# Board_4x8-Prototype_v20160405.net
KiCad netlist of a schematic drawn in EAGLE
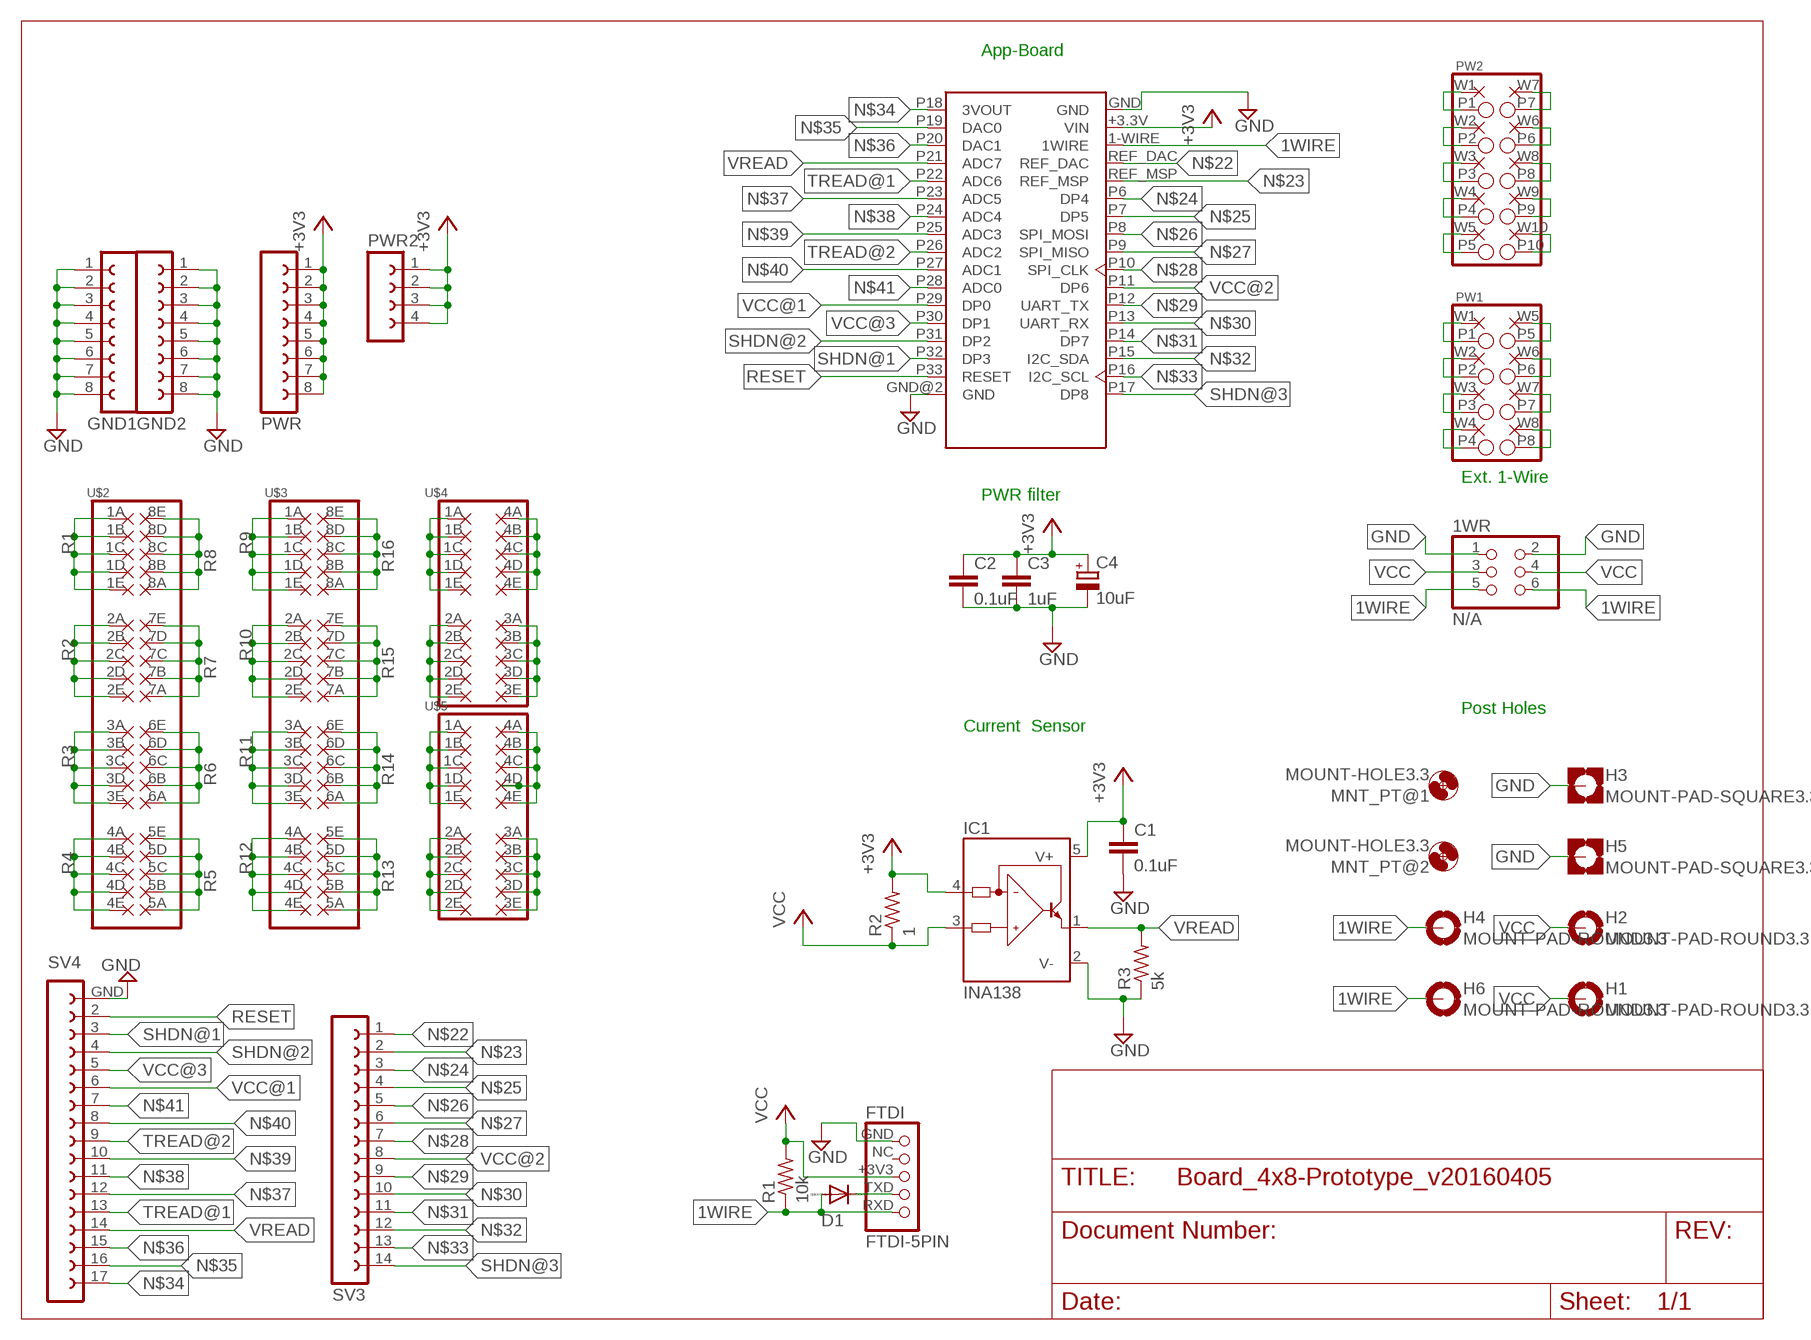
[diagram p0: schematic, sheet 1]

(export (version "E")
  (design (tool "Eeschema 10.0.6"))
  (components
    (comp (ref "1WR")
      (value "N/A")
      (footprint "eagle-import:2X03")
      (libsource (lib "eagle-import") (part "PINHD-2X3"))
    )
    (comp (ref "C1")
      (value "0.1uF")
      (footprint "eagle-import:C0805")
      (libsource (lib "eagle-import") (part "C-EUC0805"))
    )
    (comp (ref "C2")
      (value "0.1uF")
      (footprint "eagle-import:C0603")
      (libsource (lib "eagle-import") (part "C-EUC0603"))
    )
    (comp (ref "C3")
      (value "1uF")
      (footprint "eagle-import:C0603")
      (libsource (lib "eagle-import") (part "C-EUC0603"))
    )
    (comp (ref "C4")
      (value "10uF")
      (footprint "eagle-import:SMC_B")
      (libsource (lib "eagle-import") (part "CPOL-EUSMCB"))
    )
    (comp (ref "D1")
      (value "1N4148DO35-7")
      (footprint "eagle-import:DO35-7")
      (libsource (lib "eagle-import") (part "1N4148DO35-7"))
    )
    (comp (ref "FTDI")
      (value "FTDI-5PIN")
      (footprint "eagle-import:1_05X2MM")
      (libsource (lib "eagle-import") (part "FTDI-5PIN"))
    )
    (comp (ref "GND1")
      (value "FE08-1-GND")
      (footprint "eagle-import:FE08-GND")
      (libsource (lib "eagle-import") (part "FE08-1-GND"))
    )
    (comp (ref "GND2")
      (value "FE08-1-GND")
      (footprint "eagle-import:FE08-GND")
      (libsource (lib "eagle-import") (part "FE08-1-GND"))
    )
    (comp (ref "H1")
      (value "MOUNT-PAD-ROUND3.3")
      (footprint "eagle-import:3,3-PAD")
      (libsource (lib "eagle-import") (part "MOUNT-PAD-ROUND3.3"))
    )
    (comp (ref "H2")
      (value "MOUNT-PAD-ROUND3.3")
      (footprint "eagle-import:3,3-PAD")
      (libsource (lib "eagle-import") (part "MOUNT-PAD-ROUND3.3"))
    )
    (comp (ref "H3")
      (value "MOUNT-PAD-SQUARE3.3")
      (footprint "eagle-import:3,3-PAD-SQUARE")
      (libsource (lib "eagle-import") (part "MOUNT-PAD-SQUARE3.3"))
    )
    (comp (ref "H4")
      (value "MOUNT-PAD-ROUND3.3")
      (footprint "eagle-import:3,3-PAD")
      (libsource (lib "eagle-import") (part "MOUNT-PAD-ROUND3.3"))
    )
    (comp (ref "H5")
      (value "MOUNT-PAD-SQUARE3.3")
      (footprint "eagle-import:3,3-PAD-SQUARE")
      (libsource (lib "eagle-import") (part "MOUNT-PAD-SQUARE3.3"))
    )
    (comp (ref "H6")
      (value "MOUNT-PAD-ROUND3.3")
      (footprint "eagle-import:3,3-PAD")
      (libsource (lib "eagle-import") (part "MOUNT-PAD-ROUND3.3"))
    )
    (comp (ref "IC1")
      (value "INA138")
      (footprint "eagle-import:SOT23-5")
      (fields (field (name "MF") "TEXAS INSTRUMENTS") (field (name "MPN") "INA138NA/250"))
      (libsource (lib "eagle-import") (part "INA138"))
    )
    (comp (ref "MNT_PT@1")
      (value "MOUNT-HOLE3.3")
      (footprint "eagle-import:3,3")
      (libsource (lib "eagle-import") (part "MOUNT-HOLE3.3"))
    )
    (comp (ref "MNT_PT@2")
      (value "MOUNT-HOLE3.3")
      (footprint "eagle-import:3,3")
      (libsource (lib "eagle-import") (part "MOUNT-HOLE3.3"))
    )
    (comp (ref "PW1")
      (value "PIN-WIRE-2X8")
      (footprint "eagle-import:2X8")
      (libsource (lib "eagle-import") (part "PIN-WIRE-2X8"))
    )
    (comp (ref "PW2")
      (value "PIN-WIRE-2X10")
      (footprint "eagle-import:2X10")
      (libsource (lib "eagle-import") (part "PIN-WIRE-2X10"))
    )
    (comp (ref "PWR")
      (value "FE08-1")
      (footprint "eagle-import:FE08")
      (libsource (lib "eagle-import") (part "FE08-1"))
    )
    (comp (ref "PWR2")
      (value "FE04-1")
      (footprint "eagle-import:FE04-1")
      (libsource (lib "eagle-import") (part "FE04-1"))
    )
    (comp (ref "R1")
      (value "10k")
      (footprint "eagle-import:0207_7")
      (libsource (lib "eagle-import") (part "R-US_0207/7"))
    )
    (comp (ref "R2")
      (value "1")
      (footprint "eagle-import:R0603")
      (libsource (lib "eagle-import") (part "R-US_R0603"))
    )
    (comp (ref "R3")
      (value "5k")
      (footprint "eagle-import:R0603")
      (libsource (lib "eagle-import") (part "R-US_R0603"))
    )
    (comp (ref "SV3")
      (value "FE14-1_ABBO")
      (footprint "eagle-import:FE14-1_ABBO")
      (libsource (lib "eagle-import") (part "FE14-1_ABBO"))
    )
    (comp (ref "SV4")
      (value "FE17-1_ABBO")
      (footprint "eagle-import:FE17-1_ABBO")
      (libsource (lib "eagle-import") (part "FE17-1_ABBO"))
    )
    (comp (ref "U$1")
      (value "App-Board 1.2/1.3")
      (footprint "eagle-import:APPCORE_RECEIVER")
      (libsource (lib "eagle-import") (part "APP_CORE"))
    )
    (comp (ref "U$2")
      (value "PROTO-5X8")
      (footprint "eagle-import:PROTO-2X05")
      (libsource (lib "eagle-import") (part "PROTO-5X8"))
    )
    (comp (ref "U$3")
      (value "PROTO-5X8")
      (footprint "eagle-import:PROTO-2X05")
      (libsource (lib "eagle-import") (part "PROTO-5X8"))
    )
    (comp (ref "U$4")
      (value "PROTO-4X5")
      (footprint "eagle-import:PROTO-4X05")
      (libsource (lib "eagle-import") (part "PROTO-4X5"))
    )
    (comp (ref "U$5")
      (value "PROTO-4X5")
      (footprint "eagle-import:PROTO-4X05")
      (libsource (lib "eagle-import") (part "PROTO-4X5"))
    )
  )
  (nets
    (net (code "1") (name "+3V3") (class "Default")
      (node (ref "C1") (pin "1") (pinfunction "1_1") (pintype "passive"))
      (node (ref "C2") (pin "1") (pinfunction "1_1") (pintype "passive"))
      (node (ref "C3") (pin "1") (pinfunction "1_1") (pintype "passive"))
      (node (ref "C4") (pin "+") (pinfunction "+_+") (pintype "passive"))
      (node (ref "IC1") (pin "4") (pinfunction "IN-_4") (pintype "input"))
      (node (ref "IC1") (pin "5") (pinfunction "V+_5") (pintype "power_in"))
      (node (ref "PWR") (pin "1") (pinfunction "1_1") (pintype "passive"))
      (node (ref "PWR") (pin "2") (pinfunction "2_2") (pintype "passive"))
      (node (ref "PWR") (pin "3") (pinfunction "3_3") (pintype "passive"))
      (node (ref "PWR") (pin "4") (pinfunction "4_4") (pintype "passive"))
      (node (ref "PWR") (pin "5") (pinfunction "5_5") (pintype "passive"))
      (node (ref "PWR") (pin "6") (pinfunction "6_6") (pintype "passive"))
      (node (ref "PWR") (pin "7") (pinfunction "7_7") (pintype "passive"))
      (node (ref "PWR") (pin "8") (pinfunction "8_8") (pintype "passive"))
      (node (ref "PWR2") (pin "1") (pinfunction "1_1") (pintype "passive"))
      (node (ref "PWR2") (pin "2") (pinfunction "2_2") (pintype "passive"))
      (node (ref "PWR2") (pin "3") (pinfunction "3_3") (pintype "passive"))
      (node (ref "PWR2") (pin "4") (pinfunction "4_4") (pintype "passive"))
      (node (ref "R2") (pin "2") (pinfunction "2_2") (pintype "passive"))
      (node (ref "U$1") (pin "+3.3V") (pinfunction "VIN_+3.3V") (pintype "power_in"))
    )
    (net (code "2") (name "/R1") (class "Default")
      (node (ref "U$2") (pin "1A") (pinfunction "1A_1A") (pintype "passive"))
      (node (ref "U$2") (pin "1B") (pinfunction "1B_1B") (pintype "passive"))
      (node (ref "U$2") (pin "1C") (pinfunction "1C_1C") (pintype "passive"))
      (node (ref "U$2") (pin "1D") (pinfunction "1D_1D") (pintype "passive"))
      (node (ref "U$2") (pin "1E") (pinfunction "1E_1E") (pintype "passive"))
    )
    (net (code "3") (name "/R2") (class "Default")
      (node (ref "U$2") (pin "2A") (pinfunction "2A_2A") (pintype "passive"))
      (node (ref "U$2") (pin "2B") (pinfunction "2B_2B") (pintype "passive"))
      (node (ref "U$2") (pin "2C") (pinfunction "2C_2C") (pintype "passive"))
      (node (ref "U$2") (pin "2D") (pinfunction "2D_2D") (pintype "passive"))
      (node (ref "U$2") (pin "2E") (pinfunction "2E_2E") (pintype "passive"))
    )
    (net (code "4") (name "/R3") (class "Default")
      (node (ref "U$2") (pin "3A") (pinfunction "3A_3A") (pintype "passive"))
      (node (ref "U$2") (pin "3B") (pinfunction "3B_3B") (pintype "passive"))
      (node (ref "U$2") (pin "3C") (pinfunction "3C_3C") (pintype "passive"))
      (node (ref "U$2") (pin "3D") (pinfunction "3D_3D") (pintype "passive"))
      (node (ref "U$2") (pin "3E") (pinfunction "3E_3E") (pintype "passive"))
    )
    (net (code "5") (name "/R4") (class "Default")
      (node (ref "U$2") (pin "4A") (pinfunction "4A_4A") (pintype "passive"))
      (node (ref "U$2") (pin "4B") (pinfunction "4B_4B") (pintype "passive"))
      (node (ref "U$2") (pin "4C") (pinfunction "4C_4C") (pintype "passive"))
      (node (ref "U$2") (pin "4D") (pinfunction "4D_4D") (pintype "passive"))
      (node (ref "U$2") (pin "4E") (pinfunction "4E_4E") (pintype "passive"))
    )
    (net (code "6") (name "/R5") (class "Default")
      (node (ref "U$2") (pin "5A") (pinfunction "5A_5A") (pintype "passive"))
      (node (ref "U$2") (pin "5B") (pinfunction "5B_5B") (pintype "passive"))
      (node (ref "U$2") (pin "5C") (pinfunction "5C_5C") (pintype "passive"))
      (node (ref "U$2") (pin "5D") (pinfunction "5D_5D") (pintype "passive"))
      (node (ref "U$2") (pin "5E") (pinfunction "5E_5E") (pintype "passive"))
    )
    (net (code "7") (name "/R6") (class "Default")
      (node (ref "U$2") (pin "6A") (pinfunction "6A_6A") (pintype "passive"))
      (node (ref "U$2") (pin "6B") (pinfunction "6B_6B") (pintype "passive"))
      (node (ref "U$2") (pin "6C") (pinfunction "6C_6C") (pintype "passive"))
      (node (ref "U$2") (pin "6D") (pinfunction "6D_6D") (pintype "passive"))
      (node (ref "U$2") (pin "6E") (pinfunction "6E_6E") (pintype "passive"))
    )
    (net (code "8") (name "/R7") (class "Default")
      (node (ref "U$2") (pin "7A") (pinfunction "7A_7A") (pintype "passive"))
      (node (ref "U$2") (pin "7B") (pinfunction "7B_7B") (pintype "passive"))
      (node (ref "U$2") (pin "7C") (pinfunction "7C_7C") (pintype "passive"))
      (node (ref "U$2") (pin "7D") (pinfunction "7D_7D") (pintype "passive"))
      (node (ref "U$2") (pin "7E") (pinfunction "7E_7E") (pintype "passive"))
    )
    (net (code "9") (name "/R8") (class "Default")
      (node (ref "U$2") (pin "8A") (pinfunction "8A_8A") (pintype "passive"))
      (node (ref "U$2") (pin "8B") (pinfunction "8B_8B") (pintype "passive"))
      (node (ref "U$2") (pin "8C") (pinfunction "8C_8C") (pintype "passive"))
      (node (ref "U$2") (pin "8D") (pinfunction "8D_8D") (pintype "passive"))
      (node (ref "U$2") (pin "8E") (pinfunction "8E_8E") (pintype "passive"))
    )
    (net (code "10") (name "/R9") (class "Default")
      (node (ref "U$3") (pin "1A") (pinfunction "1A_1A") (pintype "passive"))
      (node (ref "U$3") (pin "1B") (pinfunction "1B_1B") (pintype "passive"))
      (node (ref "U$3") (pin "1C") (pinfunction "1C_1C") (pintype "passive"))
      (node (ref "U$3") (pin "1D") (pinfunction "1D_1D") (pintype "passive"))
      (node (ref "U$3") (pin "1E") (pinfunction "1E_1E") (pintype "passive"))
    )
    (net (code "11") (name "/R10") (class "Default")
      (node (ref "U$3") (pin "2A") (pinfunction "2A_2A") (pintype "passive"))
      (node (ref "U$3") (pin "2B") (pinfunction "2B_2B") (pintype "passive"))
      (node (ref "U$3") (pin "2C") (pinfunction "2C_2C") (pintype "passive"))
      (node (ref "U$3") (pin "2D") (pinfunction "2D_2D") (pintype "passive"))
      (node (ref "U$3") (pin "2E") (pinfunction "2E_2E") (pintype "passive"))
    )
    (net (code "12") (name "/R11") (class "Default")
      (node (ref "U$3") (pin "3A") (pinfunction "3A_3A") (pintype "passive"))
      (node (ref "U$3") (pin "3B") (pinfunction "3B_3B") (pintype "passive"))
      (node (ref "U$3") (pin "3C") (pinfunction "3C_3C") (pintype "passive"))
      (node (ref "U$3") (pin "3D") (pinfunction "3D_3D") (pintype "passive"))
      (node (ref "U$3") (pin "3E") (pinfunction "3E_3E") (pintype "passive"))
    )
    (net (code "13") (name "/R12") (class "Default")
      (node (ref "U$3") (pin "4A") (pinfunction "4A_4A") (pintype "passive"))
      (node (ref "U$3") (pin "4B") (pinfunction "4B_4B") (pintype "passive"))
      (node (ref "U$3") (pin "4C") (pinfunction "4C_4C") (pintype "passive"))
      (node (ref "U$3") (pin "4D") (pinfunction "4D_4D") (pintype "passive"))
      (node (ref "U$3") (pin "4E") (pinfunction "4E_4E") (pintype "passive"))
    )
    (net (code "14") (name "/R13") (class "Default")
      (node (ref "U$3") (pin "5A") (pinfunction "5A_5A") (pintype "passive"))
      (node (ref "U$3") (pin "5B") (pinfunction "5B_5B") (pintype "passive"))
      (node (ref "U$3") (pin "5C") (pinfunction "5C_5C") (pintype "passive"))
      (node (ref "U$3") (pin "5D") (pinfunction "5D_5D") (pintype "passive"))
      (node (ref "U$3") (pin "5E") (pinfunction "5E_5E") (pintype "passive"))
    )
    (net (code "15") (name "/R14") (class "Default")
      (node (ref "U$3") (pin "6A") (pinfunction "6A_6A") (pintype "passive"))
      (node (ref "U$3") (pin "6B") (pinfunction "6B_6B") (pintype "passive"))
      (node (ref "U$3") (pin "6C") (pinfunction "6C_6C") (pintype "passive"))
      (node (ref "U$3") (pin "6D") (pinfunction "6D_6D") (pintype "passive"))
      (node (ref "U$3") (pin "6E") (pinfunction "6E_6E") (pintype "passive"))
    )
    (net (code "16") (name "/R15") (class "Default")
      (node (ref "U$3") (pin "7A") (pinfunction "7A_7A") (pintype "passive"))
      (node (ref "U$3") (pin "7B") (pinfunction "7B_7B") (pintype "passive"))
      (node (ref "U$3") (pin "7C") (pinfunction "7C_7C") (pintype "passive"))
      (node (ref "U$3") (pin "7D") (pinfunction "7D_7D") (pintype "passive"))
      (node (ref "U$3") (pin "7E") (pinfunction "7E_7E") (pintype "passive"))
    )
    (net (code "17") (name "/R16") (class "Default")
      (node (ref "U$3") (pin "8A") (pinfunction "8A_8A") (pintype "passive"))
      (node (ref "U$3") (pin "8B") (pinfunction "8B_8B") (pintype "passive"))
      (node (ref "U$3") (pin "8C") (pinfunction "8C_8C") (pintype "passive"))
      (node (ref "U$3") (pin "8D") (pinfunction "8D_8D") (pintype "passive"))
      (node (ref "U$3") (pin "8E") (pinfunction "8E_8E") (pintype "passive"))
    )
    (net (code "18") (name "1WIRE") (class "Default")
      (node (ref "1WR") (pin "5") (pinfunction "5_5") (pintype "passive"))
      (node (ref "1WR") (pin "6") (pinfunction "6_6") (pintype "passive"))
      (node (ref "D1") (pin "A") (pinfunction "A_A") (pintype "passive"))
      (node (ref "FTDI") (pin "RXD") (pinfunction "RXD_RXD") (pintype "input"))
      (node (ref "H4") (pin "B3,3") (pinfunction "MOUNT_B3,3") (pintype "passive"))
      (node (ref "H6") (pin "B3,3") (pinfunction "MOUNT_B3,3") (pintype "passive"))
      (node (ref "R1") (pin "1") (pinfunction "1_1") (pintype "passive"))
      (node (ref "U$1") (pin "1-WIRE") (pinfunction "1WIRE_1-WIRE") (pintype "bidirectional"))
    )
    (net (code "19") (name "GND") (class "Default")
      (node (ref "1WR") (pin "1") (pinfunction "1_1") (pintype "passive"))
      (node (ref "1WR") (pin "2") (pinfunction "2_2") (pintype "passive"))
      (node (ref "C1") (pin "2") (pinfunction "2_2") (pintype "passive"))
      (node (ref "C2") (pin "2") (pinfunction "2_2") (pintype "passive"))
      (node (ref "C3") (pin "2") (pinfunction "2_2") (pintype "passive"))
      (node (ref "C4") (pin "-") (pinfunction "-_-") (pintype "passive"))
      (node (ref "FTDI") (pin "GND") (pinfunction "GND_GND") (pintype "power_in"))
      (node (ref "GND1") (pin "1") (pinfunction "1_1") (pintype "passive"))
      (node (ref "GND1") (pin "2") (pinfunction "2_2") (pintype "passive"))
      (node (ref "GND1") (pin "3") (pinfunction "3_3") (pintype "passive"))
      (node (ref "GND1") (pin "4") (pinfunction "4_4") (pintype "passive"))
      (node (ref "GND1") (pin "5") (pinfunction "5_5") (pintype "passive"))
      (node (ref "GND1") (pin "6") (pinfunction "6_6") (pintype "passive"))
      (node (ref "GND1") (pin "7") (pinfunction "7_7") (pintype "passive"))
      (node (ref "GND1") (pin "8") (pinfunction "8_8") (pintype "passive"))
      (node (ref "GND2") (pin "1") (pinfunction "1_1") (pintype "passive"))
      (node (ref "GND2") (pin "2") (pinfunction "2_2") (pintype "passive"))
      (node (ref "GND2") (pin "3") (pinfunction "3_3") (pintype "passive"))
      (node (ref "GND2") (pin "4") (pinfunction "4_4") (pintype "passive"))
      (node (ref "GND2") (pin "5") (pinfunction "5_5") (pintype "passive"))
      (node (ref "GND2") (pin "6") (pinfunction "6_6") (pintype "passive"))
      (node (ref "GND2") (pin "7") (pinfunction "7_7") (pintype "passive"))
      (node (ref "GND2") (pin "8") (pinfunction "8_8") (pintype "passive"))
      (node (ref "H3") (pin "B3,3") (pinfunction "MOUNT_B3,3") (pintype "passive"))
      (node (ref "H5") (pin "B3,3") (pinfunction "MOUNT_B3,3") (pintype "passive"))
      (node (ref "IC1") (pin "2") (pinfunction "V-_2") (pintype "power_in"))
      (node (ref "R3") (pin "1") (pinfunction "1_1") (pintype "passive"))
      (node (ref "SV4") (pin "GND") (pinfunction "GND_GND") (pintype "power_in"))
      (node (ref "U$1") (pin "GND") (pinfunction "GND_GND") (pintype "power_in"))
      (node (ref "U$1") (pin "GND@2") (pinfunction "GND_GND@2") (pintype "power_in"))
    )
    (net (code "20") (name "N$22") (class "Default")
      (node (ref "SV3") (pin "1") (pinfunction "1_1") (pintype "passive"))
      (node (ref "U$1") (pin "REF_DAC") (pinfunction "REF_DAC_REF_DAC") (pintype "input"))
    )
    (net (code "21") (name "N$23") (class "Default")
      (node (ref "SV3") (pin "2") (pinfunction "2_2") (pintype "passive"))
      (node (ref "U$1") (pin "REF_MSP") (pinfunction "REF_MSP_REF_MSP") (pintype "input"))
    )
    (net (code "22") (name "N$24") (class "Default")
      (node (ref "SV3") (pin "3") (pinfunction "3_3") (pintype "passive"))
      (node (ref "U$1") (pin "P6") (pinfunction "DP4_P6") (pintype "bidirectional"))
    )
    (net (code "23") (name "N$25") (class "Default")
      (node (ref "SV3") (pin "4") (pinfunction "4_4") (pintype "passive"))
      (node (ref "U$1") (pin "P7") (pinfunction "DP5_P7") (pintype "bidirectional"))
    )
    (net (code "24") (name "N$26") (class "Default")
      (node (ref "SV3") (pin "5") (pinfunction "5_5") (pintype "passive"))
      (node (ref "U$1") (pin "P8") (pinfunction "SPI_MOSI_P8") (pintype "bidirectional"))
    )
    (net (code "25") (name "N$27") (class "Default")
      (node (ref "SV3") (pin "6") (pinfunction "6_6") (pintype "passive"))
      (node (ref "U$1") (pin "P9") (pinfunction "SPI_MISO_P9") (pintype "bidirectional"))
    )
    (net (code "26") (name "N$28") (class "Default")
      (node (ref "SV3") (pin "7") (pinfunction "7_7") (pintype "passive"))
      (node (ref "U$1") (pin "P10") (pinfunction "SPI_CLK_P10") (pintype "bidirectional"))
    )
    (net (code "27") (name "N$29") (class "Default")
      (node (ref "SV3") (pin "9") (pinfunction "9_9") (pintype "passive"))
      (node (ref "U$1") (pin "P12") (pinfunction "UART_TX_P12") (pintype "output"))
    )
    (net (code "28") (name "N$30") (class "Default")
      (node (ref "SV3") (pin "10") (pinfunction "10_10") (pintype "passive"))
      (node (ref "U$1") (pin "P13") (pinfunction "UART_RX_P13") (pintype "input"))
    )
    (net (code "29") (name "N$31") (class "Default")
      (node (ref "SV3") (pin "11") (pinfunction "11_11") (pintype "passive"))
      (node (ref "U$1") (pin "P14") (pinfunction "DP7_P14") (pintype "bidirectional"))
    )
    (net (code "30") (name "N$32") (class "Default")
      (node (ref "SV3") (pin "12") (pinfunction "12_12") (pintype "passive"))
      (node (ref "U$1") (pin "P15") (pinfunction "I2C_SDA_P15") (pintype "bidirectional"))
    )
    (net (code "31") (name "N$33") (class "Default")
      (node (ref "SV3") (pin "13") (pinfunction "13_13") (pintype "passive"))
      (node (ref "U$1") (pin "P16") (pinfunction "I2C_SCL_P16") (pintype "bidirectional"))
    )
    (net (code "32") (name "N$34") (class "Default")
      (node (ref "SV4") (pin "17") (pinfunction "17_17") (pintype "passive"))
      (node (ref "U$1") (pin "P18") (pinfunction "3VOUT_P18") (pintype "output"))
    )
    (net (code "33") (name "N$35") (class "Default")
      (node (ref "SV4") (pin "16") (pinfunction "16_16") (pintype "passive"))
      (node (ref "U$1") (pin "P19") (pinfunction "DAC0_P19") (pintype "bidirectional"))
    )
    (net (code "34") (name "N$36") (class "Default")
      (node (ref "SV4") (pin "15") (pinfunction "15_15") (pintype "passive"))
      (node (ref "U$1") (pin "P20") (pinfunction "DAC1_P20") (pintype "bidirectional"))
    )
    (net (code "35") (name "N$37") (class "Default")
      (node (ref "SV4") (pin "12") (pinfunction "12_12") (pintype "passive"))
      (node (ref "U$1") (pin "P23") (pinfunction "ADC5_P23") (pintype "input"))
    )
    (net (code "36") (name "N$38") (class "Default")
      (node (ref "SV4") (pin "11") (pinfunction "11_11") (pintype "passive"))
      (node (ref "U$1") (pin "P24") (pinfunction "ADC4_P24") (pintype "input"))
    )
    (net (code "37") (name "N$39") (class "Default")
      (node (ref "SV4") (pin "10") (pinfunction "10_10") (pintype "passive"))
      (node (ref "U$1") (pin "P25") (pinfunction "ADC3_P25") (pintype "input"))
    )
    (net (code "38") (name "N$40") (class "Default")
      (node (ref "SV4") (pin "8") (pinfunction "8_8") (pintype "passive"))
      (node (ref "U$1") (pin "P27") (pinfunction "ADC1_P27") (pintype "input"))
    )
    (net (code "39") (name "N$41") (class "Default")
      (node (ref "SV4") (pin "7") (pinfunction "7_7") (pintype "passive"))
      (node (ref "U$1") (pin "P28") (pinfunction "ADC0_P28") (pintype "input"))
    )
    (net (code "40") (name "Net-(D1-PadC)") (class "Default")
      (node (ref "D1") (pin "C") (pinfunction "C_C") (pintype "passive"))
      (node (ref "FTDI") (pin "TXD") (pinfunction "TXD_TXD") (pintype "output"))
    )
    (net (code "41") (name "Net-(PW1-P$1)") (class "Default")
      (node (ref "PW1") (pin "P1") (pinfunction "P$1_P1") (pintype "passive"))
      (node (ref "PW1") (pin "W1") (pinfunction "W$1_W1") (pintype "passive"))
    )
    (net (code "42") (name "Net-(PW1-P$2)") (class "Default")
      (node (ref "PW1") (pin "P2") (pinfunction "P$2_P2") (pintype "passive"))
      (node (ref "PW1") (pin "W2") (pinfunction "W$2_W2") (pintype "passive"))
    )
    (net (code "43") (name "Net-(PW1-P$3)") (class "Default")
      (node (ref "PW1") (pin "P3") (pinfunction "P$3_P3") (pintype "passive"))
      (node (ref "PW1") (pin "W3") (pinfunction "W$3_W3") (pintype "passive"))
    )
    (net (code "44") (name "Net-(PW1-P$4)") (class "Default")
      (node (ref "PW1") (pin "P4") (pinfunction "P$4_P4") (pintype "passive"))
      (node (ref "PW1") (pin "W4") (pinfunction "W$4_W4") (pintype "passive"))
    )
    (net (code "45") (name "Net-(PW1-P$5)") (class "Default")
      (node (ref "PW1") (pin "P5") (pinfunction "P$5_P5") (pintype "passive"))
      (node (ref "PW1") (pin "W5") (pinfunction "W$5_W5") (pintype "passive"))
    )
    (net (code "46") (name "Net-(PW1-P$6)") (class "Default")
      (node (ref "PW1") (pin "P6") (pinfunction "P$6_P6") (pintype "passive"))
      (node (ref "PW1") (pin "W6") (pinfunction "W$6_W6") (pintype "passive"))
    )
    (net (code "47") (name "Net-(PW1-P$7)") (class "Default")
      (node (ref "PW1") (pin "P7") (pinfunction "P$7_P7") (pintype "passive"))
      (node (ref "PW1") (pin "W7") (pinfunction "W$7_W7") (pintype "passive"))
    )
    (net (code "48") (name "Net-(PW1-P$8)") (class "Default")
      (node (ref "PW1") (pin "P8") (pinfunction "P$8_P8") (pintype "passive"))
      (node (ref "PW1") (pin "W8") (pinfunction "W$8_W8") (pintype "passive"))
    )
    (net (code "49") (name "Net-(PW2-P$1)") (class "Default")
      (node (ref "PW2") (pin "P1") (pinfunction "P$1_P1") (pintype "passive"))
      (node (ref "PW2") (pin "W1") (pinfunction "W$1_W1") (pintype "passive"))
    )
    (net (code "50") (name "Net-(PW2-P$2)") (class "Default")
      (node (ref "PW2") (pin "P2") (pinfunction "P$2_P2") (pintype "passive"))
      (node (ref "PW2") (pin "W2") (pinfunction "W$2_W2") (pintype "passive"))
    )
    (net (code "51") (name "Net-(PW2-P$3)") (class "Default")
      (node (ref "PW2") (pin "P3") (pinfunction "P$3_P3") (pintype "passive"))
      (node (ref "PW2") (pin "W3") (pinfunction "W$3_W3") (pintype "passive"))
    )
    (net (code "52") (name "Net-(PW2-P$4)") (class "Default")
      (node (ref "PW2") (pin "P4") (pinfunction "P$4_P4") (pintype "passive"))
      (node (ref "PW2") (pin "W4") (pinfunction "W$4_W4") (pintype "passive"))
    )
    (net (code "53") (name "Net-(PW2-P$5)") (class "Default")
      (node (ref "PW2") (pin "P5") (pinfunction "P$5_P5") (pintype "passive"))
      (node (ref "PW2") (pin "W5") (pinfunction "W$5_W5") (pintype "passive"))
    )
    (net (code "54") (name "Net-(PW2-P$6)") (class "Default")
      (node (ref "PW2") (pin "P6") (pinfunction "P$6_P6") (pintype "passive"))
      (node (ref "PW2") (pin "W6") (pinfunction "W$6_W6") (pintype "passive"))
    )
    (net (code "55") (name "Net-(PW2-P$7)") (class "Default")
      (node (ref "PW2") (pin "P7") (pinfunction "P$7_P7") (pintype "passive"))
      (node (ref "PW2") (pin "W7") (pinfunction "W$7_W7") (pintype "passive"))
    )
    (net (code "56") (name "Net-(PW2-P$8)") (class "Default")
      (node (ref "PW2") (pin "P8") (pinfunction "P$8_P8") (pintype "passive"))
      (node (ref "PW2") (pin "W8") (pinfunction "W$8_W8") (pintype "passive"))
    )
    (net (code "57") (name "Net-(PW2-P$9)") (class "Default")
      (node (ref "PW2") (pin "P9") (pinfunction "P$9_P9") (pintype "passive"))
      (node (ref "PW2") (pin "W9") (pinfunction "W$9_W9") (pintype "passive"))
    )
    (net (code "58") (name "Net-(PW2-P$10)") (class "Default")
      (node (ref "PW2") (pin "P10") (pinfunction "P$10_P10") (pintype "passive"))
      (node (ref "PW2") (pin "W10") (pinfunction "W$10_W10") (pintype "passive"))
    )
    (net (code "59") (name "Net-(U$4-Pad1A)") (class "Default")
      (node (ref "U$4") (pin "1A") (pinfunction "1A_1A") (pintype "passive"))
      (node (ref "U$4") (pin "1B") (pinfunction "1B_1B") (pintype "passive"))
      (node (ref "U$4") (pin "1C") (pinfunction "1C_1C") (pintype "passive"))
      (node (ref "U$4") (pin "1D") (pinfunction "1D_1D") (pintype "passive"))
      (node (ref "U$4") (pin "1E") (pinfunction "1E_1E") (pintype "passive"))
    )
    (net (code "60") (name "Net-(U$4-Pad2A)") (class "Default")
      (node (ref "U$4") (pin "2A") (pinfunction "2A_2A") (pintype "passive"))
      (node (ref "U$4") (pin "2B") (pinfunction "2B_2B") (pintype "passive"))
      (node (ref "U$4") (pin "2C") (pinfunction "2C_2C") (pintype "passive"))
      (node (ref "U$4") (pin "2D") (pinfunction "2D_2D") (pintype "passive"))
      (node (ref "U$4") (pin "2E") (pinfunction "2E_2E") (pintype "passive"))
    )
    (net (code "61") (name "Net-(U$4-Pad3A)") (class "Default")
      (node (ref "U$4") (pin "3A") (pinfunction "3A_3A") (pintype "passive"))
      (node (ref "U$4") (pin "3B") (pinfunction "3B_3B") (pintype "passive"))
      (node (ref "U$4") (pin "3C") (pinfunction "3C_3C") (pintype "passive"))
      (node (ref "U$4") (pin "3D") (pinfunction "3D_3D") (pintype "passive"))
      (node (ref "U$4") (pin "3E") (pinfunction "3E_3E") (pintype "passive"))
    )
    (net (code "62") (name "Net-(U$4-Pad4A)") (class "Default")
      (node (ref "U$4") (pin "4A") (pinfunction "4A_4A") (pintype "passive"))
      (node (ref "U$4") (pin "4B") (pinfunction "4B_4B") (pintype "passive"))
      (node (ref "U$4") (pin "4C") (pinfunction "4C_4C") (pintype "passive"))
      (node (ref "U$4") (pin "4D") (pinfunction "4D_4D") (pintype "passive"))
      (node (ref "U$4") (pin "4E") (pinfunction "4E_4E") (pintype "passive"))
    )
    (net (code "63") (name "Net-(U$5-Pad1A)") (class "Default")
      (node (ref "U$5") (pin "1A") (pinfunction "1A_1A") (pintype "passive"))
      (node (ref "U$5") (pin "1B") (pinfunction "1B_1B") (pintype "passive"))
      (node (ref "U$5") (pin "1C") (pinfunction "1C_1C") (pintype "passive"))
      (node (ref "U$5") (pin "1D") (pinfunction "1D_1D") (pintype "passive"))
      (node (ref "U$5") (pin "1E") (pinfunction "1E_1E") (pintype "passive"))
    )
    (net (code "64") (name "Net-(U$5-Pad2A)") (class "Default")
      (node (ref "U$5") (pin "2A") (pinfunction "2A_2A") (pintype "passive"))
      (node (ref "U$5") (pin "2B") (pinfunction "2B_2B") (pintype "passive"))
      (node (ref "U$5") (pin "2C") (pinfunction "2C_2C") (pintype "passive"))
      (node (ref "U$5") (pin "2D") (pinfunction "2D_2D") (pintype "passive"))
      (node (ref "U$5") (pin "2E") (pinfunction "2E_2E") (pintype "passive"))
    )
    (net (code "65") (name "Net-(U$5-Pad3A)") (class "Default")
      (node (ref "U$5") (pin "3A") (pinfunction "3A_3A") (pintype "passive"))
      (node (ref "U$5") (pin "3B") (pinfunction "3B_3B") (pintype "passive"))
      (node (ref "U$5") (pin "3C") (pinfunction "3C_3C") (pintype "passive"))
      (node (ref "U$5") (pin "3D") (pinfunction "3D_3D") (pintype "passive"))
      (node (ref "U$5") (pin "3E") (pinfunction "3E_3E") (pintype "passive"))
    )
    (net (code "66") (name "Net-(U$5-Pad4A)") (class "Default")
      (node (ref "U$5") (pin "4A") (pinfunction "4A_4A") (pintype "passive"))
      (node (ref "U$5") (pin "4B") (pinfunction "4B_4B") (pintype "passive"))
      (node (ref "U$5") (pin "4C") (pinfunction "4C_4C") (pintype "passive"))
      (node (ref "U$5") (pin "4D") (pinfunction "4D_4D") (pintype "passive"))
      (node (ref "U$5") (pin "4E") (pinfunction "4E_4E") (pintype "passive"))
    )
    (net (code "67") (name "RESET") (class "Default")
      (node (ref "SV4") (pin "2") (pinfunction "2_2") (pintype "passive"))
      (node (ref "U$1") (pin "P33") (pinfunction "RESET_P33") (pintype "bidirectional"))
    )
    (net (code "68") (name "SHDN@1") (class "Default")
      (node (ref "SV4") (pin "3") (pinfunction "3_3") (pintype "passive"))
      (node (ref "U$1") (pin "P32") (pinfunction "DP3_P32") (pintype "bidirectional"))
    )
    (net (code "69") (name "SHDN@2") (class "Default")
      (node (ref "SV4") (pin "4") (pinfunction "4_4") (pintype "passive"))
      (node (ref "U$1") (pin "P31") (pinfunction "DP2_P31") (pintype "bidirectional"))
    )
    (net (code "70") (name "SHDN@3") (class "Default")
      (node (ref "SV3") (pin "14") (pinfunction "14_14") (pintype "passive"))
      (node (ref "U$1") (pin "P17") (pinfunction "DP8_P17") (pintype "bidirectional"))
    )
    (net (code "71") (name "TREAD@1") (class "Default")
      (node (ref "SV4") (pin "13") (pinfunction "13_13") (pintype "passive"))
      (node (ref "U$1") (pin "P22") (pinfunction "ADC6_P22") (pintype "input"))
    )
    (net (code "72") (name "TREAD@2") (class "Default")
      (node (ref "SV4") (pin "9") (pinfunction "9_9") (pintype "passive"))
      (node (ref "U$1") (pin "P26") (pinfunction "ADC2_P26") (pintype "input"))
    )
    (net (code "73") (name "VCC") (class "Default")
      (node (ref "1WR") (pin "3") (pinfunction "3_3") (pintype "passive"))
      (node (ref "1WR") (pin "4") (pinfunction "4_4") (pintype "passive"))
      (node (ref "FTDI") (pin "+3V3") (pinfunction "+3V3_+3V3") (pintype "power_in"))
      (node (ref "H1") (pin "B3,3") (pinfunction "MOUNT_B3,3") (pintype "passive"))
      (node (ref "H2") (pin "B3,3") (pinfunction "MOUNT_B3,3") (pintype "passive"))
      (node (ref "IC1") (pin "3") (pinfunction "IN+_3") (pintype "input"))
      (node (ref "R1") (pin "2") (pinfunction "2_2") (pintype "passive"))
      (node (ref "R2") (pin "1") (pinfunction "1_1") (pintype "passive"))
    )
    (net (code "74") (name "VCC@1") (class "Default")
      (node (ref "SV4") (pin "6") (pinfunction "6_6") (pintype "passive"))
      (node (ref "U$1") (pin "P29") (pinfunction "DP0_P29") (pintype "bidirectional"))
    )
    (net (code "75") (name "VCC@2") (class "Default")
      (node (ref "SV3") (pin "8") (pinfunction "8_8") (pintype "passive"))
      (node (ref "U$1") (pin "P11") (pinfunction "DP6_P11") (pintype "bidirectional"))
    )
    (net (code "76") (name "VCC@3") (class "Default")
      (node (ref "SV4") (pin "5") (pinfunction "5_5") (pintype "passive"))
      (node (ref "U$1") (pin "P30") (pinfunction "DP1_P30") (pintype "bidirectional"))
    )
    (net (code "77") (name "VREAD") (class "Default")
      (node (ref "IC1") (pin "1") (pinfunction "OUT_1") (pintype "output"))
      (node (ref "R3") (pin "2") (pinfunction "2_2") (pintype "passive"))
      (node (ref "SV4") (pin "14") (pinfunction "14_14") (pintype "passive"))
      (node (ref "U$1") (pin "P21") (pinfunction "ADC7_P21") (pintype "input"))
    )
    (net (code "78") (name "unconnected-(FTDI-PadNC)") (class "Default")
      (node (ref "FTDI") (pin "NC") (pinfunction "NC_NC") (pintype "no_connect"))
    )
  )
)
